# Arduino_MEGA_2560-Rev3_Shield.net
KiCad netlist of a schematic drawn in EAGLE
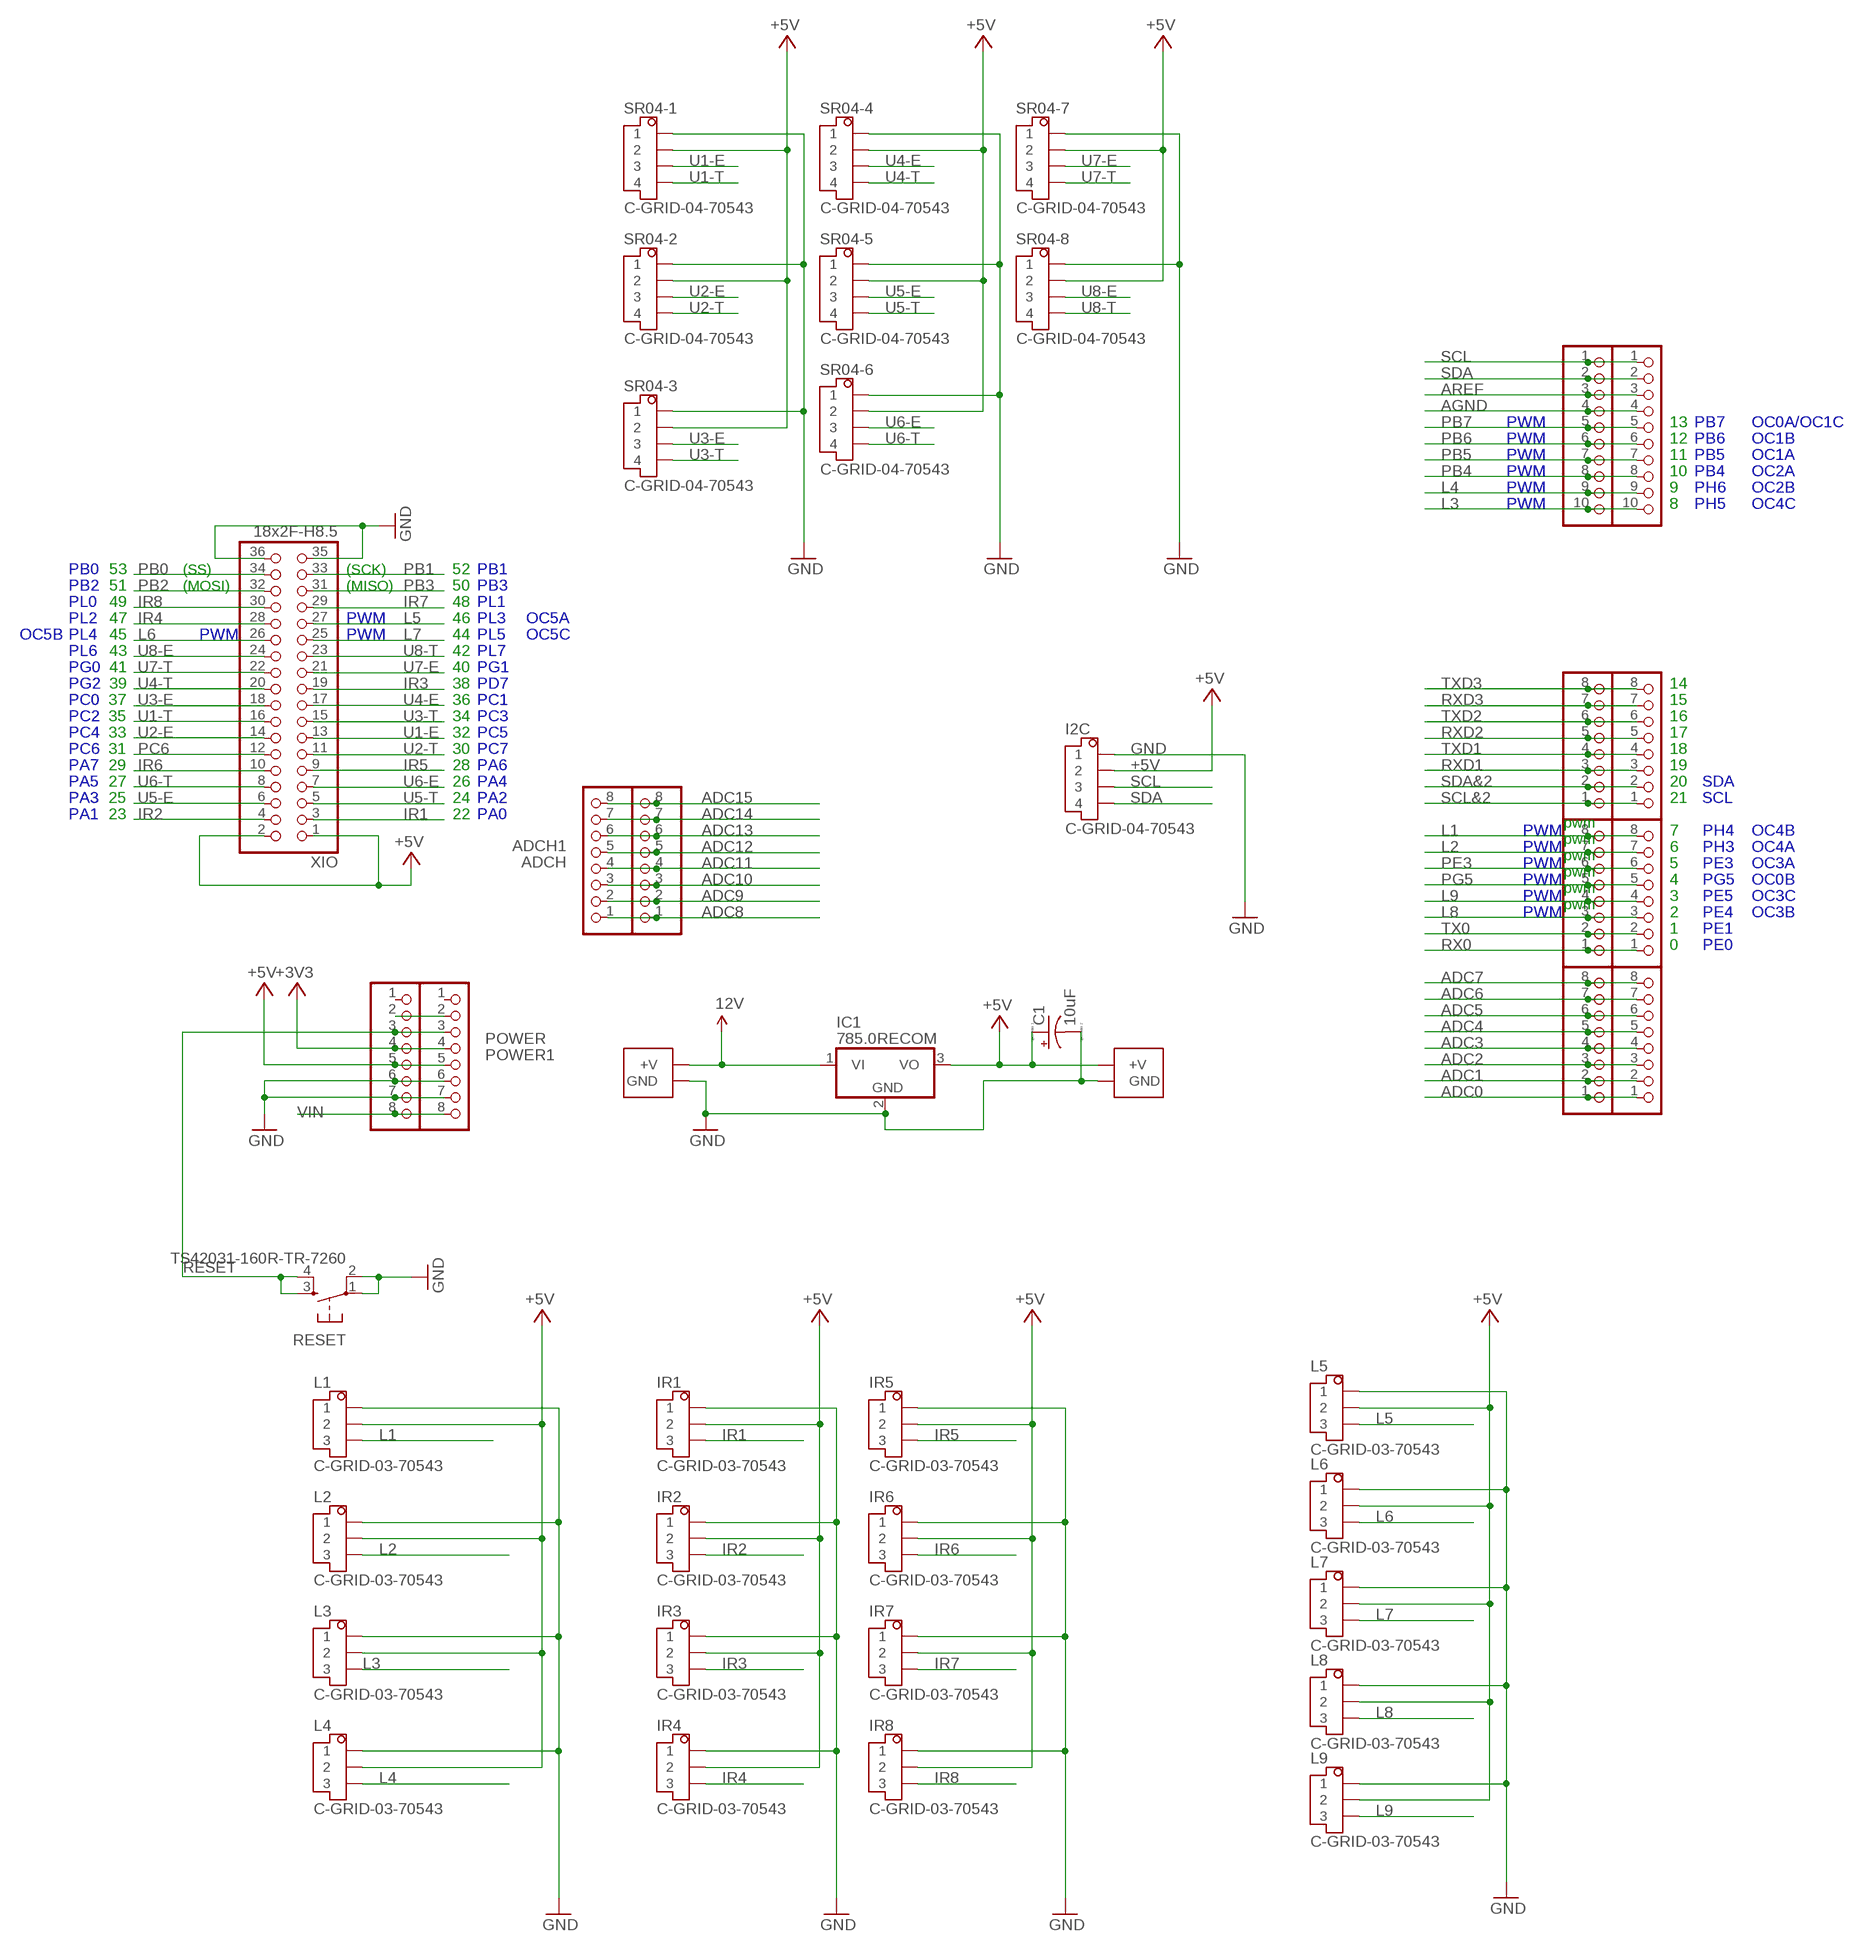
[diagram p0: schematic, sheet 1]

(export (version "E")
  (design (tool "Eeschema 10.0.6"))
  (components
    (comp (ref "ADCH")
      (value "8x1F-H8.5")
      (footprint "eagle-import:1X08")
      (libsource (lib "eagle-import") (part "PINHD-1X8"))
    )
    (comp (ref "ADCH1")
      (value "8x1F-H8.5")
      (footprint "eagle-import:1X08")
      (libsource (lib "eagle-import") (part "PINHD-1X8"))
    )
    (comp (ref "ADCL")
      (value "8x1F-H8.5")
      (footprint "eagle-import:1X08")
      (libsource (lib "eagle-import") (part "PINHD-1X8"))
    )
    (comp (ref "ADCL1")
      (value "8x1F-H8.5")
      (footprint "eagle-import:1X08")
      (libsource (lib "eagle-import") (part "PINHD-1X8"))
    )
    (comp (ref "C1")
      (value "10uF")
      (footprint "eagle-import:CT6032")
      (libsource (lib "eagle-import") (part "CPOL-USCT6032"))
    )
    (comp (ref "COMMUNICATION")
      (value "8x1F-H8.5")
      (footprint "eagle-import:1X08")
      (libsource (lib "eagle-import") (part "PINHD-1X8"))
    )
    (comp (ref "COMMUNICATION1")
      (value "8x1F-H8.5")
      (footprint "eagle-import:1X08")
      (libsource (lib "eagle-import") (part "PINHD-1X8"))
    )
    (comp (ref "I2C")
      (value "C-GRID-04-70543")
      (footprint "eagle-import:70543-04")
      (libsource (lib "eagle-import") (part "C-GRID-04-70543"))
    )
    (comp (ref "IC1")
      (value "785.0RECOM")
      (footprint "eagle-import:RECOM-78E")
      (libsource (lib "eagle-import") (part "78RECOM5.0"))
    )
    (comp (ref "IR1")
      (value "C-GRID-03-70543")
      (footprint "eagle-import:70543-03")
      (libsource (lib "eagle-import") (part "C-GRID-03-70543"))
    )
    (comp (ref "IR2")
      (value "C-GRID-03-70543")
      (footprint "eagle-import:70543-03")
      (libsource (lib "eagle-import") (part "C-GRID-03-70543"))
    )
    (comp (ref "IR3")
      (value "C-GRID-03-70543")
      (footprint "eagle-import:70543-03")
      (libsource (lib "eagle-import") (part "C-GRID-03-70543"))
    )
    (comp (ref "IR4")
      (value "C-GRID-03-70543")
      (footprint "eagle-import:70543-03")
      (libsource (lib "eagle-import") (part "C-GRID-03-70543"))
    )
    (comp (ref "IR5")
      (value "C-GRID-03-70543")
      (footprint "eagle-import:70543-03")
      (libsource (lib "eagle-import") (part "C-GRID-03-70543"))
    )
    (comp (ref "IR6")
      (value "C-GRID-03-70543")
      (footprint "eagle-import:70543-03")
      (libsource (lib "eagle-import") (part "C-GRID-03-70543"))
    )
    (comp (ref "IR7")
      (value "C-GRID-03-70543")
      (footprint "eagle-import:70543-03")
      (libsource (lib "eagle-import") (part "C-GRID-03-70543"))
    )
    (comp (ref "IR8")
      (value "C-GRID-03-70543")
      (footprint "eagle-import:70543-03")
      (libsource (lib "eagle-import") (part "C-GRID-03-70543"))
    )
    (comp (ref "JP1")
      (value "10x1F-H8.5")
      (footprint "eagle-import:1X10")
      (libsource (lib "eagle-import") (part "PINHD-1X10_ARD"))
    )
    (comp (ref "JP6")
      (value "10x1F-H8.5")
      (footprint "eagle-import:1X10")
      (libsource (lib "eagle-import") (part "PINHD-1X10_ARD"))
    )
    (comp (ref "L1")
      (value "C-GRID-03-70543")
      (footprint "eagle-import:70543-03")
      (libsource (lib "eagle-import") (part "C-GRID-03-70543"))
    )
    (comp (ref "L2")
      (value "C-GRID-03-70543")
      (footprint "eagle-import:70543-03")
      (libsource (lib "eagle-import") (part "C-GRID-03-70543"))
    )
    (comp (ref "L3")
      (value "C-GRID-03-70543")
      (footprint "eagle-import:70543-03")
      (libsource (lib "eagle-import") (part "C-GRID-03-70543"))
    )
    (comp (ref "L4")
      (value "C-GRID-03-70543")
      (footprint "eagle-import:70543-03")
      (libsource (lib "eagle-import") (part "C-GRID-03-70543"))
    )
    (comp (ref "L5")
      (value "C-GRID-03-70543")
      (footprint "eagle-import:70543-03")
      (libsource (lib "eagle-import") (part "C-GRID-03-70543"))
    )
    (comp (ref "L6")
      (value "C-GRID-03-70543")
      (footprint "eagle-import:70543-03")
      (libsource (lib "eagle-import") (part "C-GRID-03-70543"))
    )
    (comp (ref "L7")
      (value "C-GRID-03-70543")
      (footprint "eagle-import:70543-03")
      (libsource (lib "eagle-import") (part "C-GRID-03-70543"))
    )
    (comp (ref "L8")
      (value "C-GRID-03-70543")
      (footprint "eagle-import:70543-03")
      (libsource (lib "eagle-import") (part "C-GRID-03-70543"))
    )
    (comp (ref "L9")
      (value "C-GRID-03-70543")
      (footprint "eagle-import:70543-03")
      (libsource (lib "eagle-import") (part "C-GRID-03-70543"))
    )
    (comp (ref "POWER")
      (value "8x1F-H8.5")
      (footprint "eagle-import:1X08")
      (libsource (lib "eagle-import") (part "PINHD-1X8"))
    )
    (comp (ref "POWER1")
      (value "8x1F-H8.5")
      (footprint "eagle-import:1X08")
      (libsource (lib "eagle-import") (part "PINHD-1X8"))
    )
    (comp (ref "PWML")
      (value "8x1F-H8.5")
      (footprint "eagle-import:1X08")
      (libsource (lib "eagle-import") (part "PINHD-1X8"))
    )
    (comp (ref "PWML1")
      (value "8x1F-H8.5")
      (footprint "eagle-import:1X08")
      (libsource (lib "eagle-import") (part "PINHD-1X8"))
    )
    (comp (ref "RESET")
      (value "TS42031-160R-TR-7260")
      (footprint "eagle-import:TACTILE-PTH")
      (libsource (lib "eagle-import") (part "TAC_SWITCHPTH"))
    )
    (comp (ref "SR04-1")
      (value "C-GRID-04-70543")
      (footprint "eagle-import:70543-04")
      (libsource (lib "eagle-import") (part "C-GRID-04-70543"))
    )
    (comp (ref "SR04-2")
      (value "C-GRID-04-70543")
      (footprint "eagle-import:70543-04")
      (libsource (lib "eagle-import") (part "C-GRID-04-70543"))
    )
    (comp (ref "SR04-3")
      (value "C-GRID-04-70543")
      (footprint "eagle-import:70543-04")
      (libsource (lib "eagle-import") (part "C-GRID-04-70543"))
    )
    (comp (ref "SR04-4")
      (value "C-GRID-04-70543")
      (footprint "eagle-import:70543-04")
      (libsource (lib "eagle-import") (part "C-GRID-04-70543"))
    )
    (comp (ref "SR04-5")
      (value "C-GRID-04-70543")
      (footprint "eagle-import:70543-04")
      (libsource (lib "eagle-import") (part "C-GRID-04-70543"))
    )
    (comp (ref "SR04-6")
      (value "C-GRID-04-70543")
      (footprint "eagle-import:70543-04")
      (libsource (lib "eagle-import") (part "C-GRID-04-70543"))
    )
    (comp (ref "SR04-7")
      (value "C-GRID-04-70543")
      (footprint "eagle-import:70543-04")
      (libsource (lib "eagle-import") (part "C-GRID-04-70543"))
    )
    (comp (ref "SR04-8")
      (value "C-GRID-04-70543")
      (footprint "eagle-import:70543-04")
      (libsource (lib "eagle-import") (part "C-GRID-04-70543"))
    )
    (comp (ref "U$1")
      (value "POWERIN")
      (footprint "eagle-import:1825640000")
      (libsource (lib "eagle-import") (part "POWERIN"))
    )
    (comp (ref "U$2")
      (value "POWERIN")
      (footprint "eagle-import:1825640000")
      (libsource (lib "eagle-import") (part "POWERIN"))
    )
    (comp (ref "XIO")
      (value "18x2F-H8.5")
      (footprint "eagle-import:2X18")
      (libsource (lib "eagle-import") (part "PINHD-2X18"))
    )
  )
  (nets
    (net (code "1") (name "+3V3") (class "Default")
      (node (ref "POWER") (pin "4") (pinfunction "4_4") (pintype "passive"))
      (node (ref "POWER1") (pin "4") (pinfunction "4_4") (pintype "passive"))
    )
    (net (code "2") (name "+5V") (class "Default")
      (node (ref "C1") (pin "+") (pinfunction "+_+") (pintype "passive"))
      (node (ref "I2C") (pin "2") (pinfunction "2_2") (pintype "passive"))
      (node (ref "IC1") (pin "3") (pinfunction "VO_3") (pintype "passive"))
      (node (ref "IR1") (pin "2") (pinfunction "2_2") (pintype "passive"))
      (node (ref "IR2") (pin "2") (pinfunction "2_2") (pintype "passive"))
      (node (ref "IR3") (pin "2") (pinfunction "2_2") (pintype "passive"))
      (node (ref "IR4") (pin "2") (pinfunction "2_2") (pintype "passive"))
      (node (ref "IR5") (pin "2") (pinfunction "2_2") (pintype "passive"))
      (node (ref "IR6") (pin "2") (pinfunction "2_2") (pintype "passive"))
      (node (ref "IR7") (pin "2") (pinfunction "2_2") (pintype "passive"))
      (node (ref "IR8") (pin "2") (pinfunction "2_2") (pintype "passive"))
      (node (ref "L1") (pin "2") (pinfunction "2_2") (pintype "passive"))
      (node (ref "L2") (pin "2") (pinfunction "2_2") (pintype "passive"))
      (node (ref "L3") (pin "2") (pinfunction "2_2") (pintype "passive"))
      (node (ref "L4") (pin "2") (pinfunction "2_2") (pintype "passive"))
      (node (ref "L5") (pin "2") (pinfunction "2_2") (pintype "passive"))
      (node (ref "L6") (pin "2") (pinfunction "2_2") (pintype "passive"))
      (node (ref "L7") (pin "2") (pinfunction "2_2") (pintype "passive"))
      (node (ref "L8") (pin "2") (pinfunction "2_2") (pintype "passive"))
      (node (ref "L9") (pin "2") (pinfunction "2_2") (pintype "passive"))
      (node (ref "POWER") (pin "5") (pinfunction "5_5") (pintype "passive"))
      (node (ref "POWER1") (pin "5") (pinfunction "5_5") (pintype "passive"))
      (node (ref "SR04-1") (pin "2") (pinfunction "2_2") (pintype "passive"))
      (node (ref "SR04-2") (pin "2") (pinfunction "2_2") (pintype "passive"))
      (node (ref "SR04-3") (pin "2") (pinfunction "2_2") (pintype "passive"))
      (node (ref "SR04-4") (pin "2") (pinfunction "2_2") (pintype "passive"))
      (node (ref "SR04-5") (pin "2") (pinfunction "2_2") (pintype "passive"))
      (node (ref "SR04-6") (pin "2") (pinfunction "2_2") (pintype "passive"))
      (node (ref "SR04-7") (pin "2") (pinfunction "2_2") (pintype "passive"))
      (node (ref "SR04-8") (pin "2") (pinfunction "2_2") (pintype "passive"))
      (node (ref "U$2") (pin "B1") (pinfunction "+V_B1") (pintype "bidirectional"))
      (node (ref "U$2") (pin "B2") (pinfunction "+V_B2") (pintype "bidirectional"))
      (node (ref "XIO") (pin "1") (pinfunction "1_1") (pintype "passive"))
      (node (ref "XIO") (pin "2") (pinfunction "2_2") (pintype "passive"))
    )
    (net (code "3") (name "/ADC0") (class "Default")
      (node (ref "ADCL") (pin "1") (pinfunction "1_1") (pintype "passive"))
      (node (ref "ADCL1") (pin "1") (pinfunction "1_1") (pintype "passive"))
    )
    (net (code "4") (name "/ADC1") (class "Default")
      (node (ref "ADCL") (pin "2") (pinfunction "2_2") (pintype "passive"))
      (node (ref "ADCL1") (pin "2") (pinfunction "2_2") (pintype "passive"))
    )
    (net (code "5") (name "/ADC2") (class "Default")
      (node (ref "ADCL") (pin "3") (pinfunction "3_3") (pintype "passive"))
      (node (ref "ADCL1") (pin "3") (pinfunction "3_3") (pintype "passive"))
    )
    (net (code "6") (name "/ADC3") (class "Default")
      (node (ref "ADCL") (pin "4") (pinfunction "4_4") (pintype "passive"))
      (node (ref "ADCL1") (pin "4") (pinfunction "4_4") (pintype "passive"))
    )
    (net (code "7") (name "/ADC4") (class "Default")
      (node (ref "ADCL") (pin "5") (pinfunction "5_5") (pintype "passive"))
      (node (ref "ADCL1") (pin "5") (pinfunction "5_5") (pintype "passive"))
    )
    (net (code "8") (name "/ADC5") (class "Default")
      (node (ref "ADCL") (pin "6") (pinfunction "6_6") (pintype "passive"))
      (node (ref "ADCL1") (pin "6") (pinfunction "6_6") (pintype "passive"))
    )
    (net (code "9") (name "/ADC6") (class "Default")
      (node (ref "ADCL") (pin "7") (pinfunction "7_7") (pintype "passive"))
      (node (ref "ADCL1") (pin "7") (pinfunction "7_7") (pintype "passive"))
    )
    (net (code "10") (name "/ADC7") (class "Default")
      (node (ref "ADCL") (pin "8") (pinfunction "8_8") (pintype "passive"))
      (node (ref "ADCL1") (pin "8") (pinfunction "8_8") (pintype "passive"))
    )
    (net (code "11") (name "/ADC8") (class "Default")
      (node (ref "ADCH") (pin "1") (pinfunction "1_1") (pintype "passive"))
      (node (ref "ADCH1") (pin "1") (pinfunction "1_1") (pintype "passive"))
    )
    (net (code "12") (name "/ADC9") (class "Default")
      (node (ref "ADCH") (pin "2") (pinfunction "2_2") (pintype "passive"))
      (node (ref "ADCH1") (pin "2") (pinfunction "2_2") (pintype "passive"))
    )
    (net (code "13") (name "/ADC10") (class "Default")
      (node (ref "ADCH") (pin "3") (pinfunction "3_3") (pintype "passive"))
      (node (ref "ADCH1") (pin "3") (pinfunction "3_3") (pintype "passive"))
    )
    (net (code "14") (name "/ADC11") (class "Default")
      (node (ref "ADCH") (pin "4") (pinfunction "4_4") (pintype "passive"))
      (node (ref "ADCH1") (pin "4") (pinfunction "4_4") (pintype "passive"))
    )
    (net (code "15") (name "/ADC12") (class "Default")
      (node (ref "ADCH") (pin "5") (pinfunction "5_5") (pintype "passive"))
      (node (ref "ADCH1") (pin "5") (pinfunction "5_5") (pintype "passive"))
    )
    (net (code "16") (name "/ADC13") (class "Default")
      (node (ref "ADCH") (pin "6") (pinfunction "6_6") (pintype "passive"))
      (node (ref "ADCH1") (pin "6") (pinfunction "6_6") (pintype "passive"))
    )
    (net (code "17") (name "/ADC14") (class "Default")
      (node (ref "ADCH") (pin "7") (pinfunction "7_7") (pintype "passive"))
      (node (ref "ADCH1") (pin "7") (pinfunction "7_7") (pintype "passive"))
    )
    (net (code "18") (name "/ADC15") (class "Default")
      (node (ref "ADCH") (pin "8") (pinfunction "8_8") (pintype "passive"))
      (node (ref "ADCH1") (pin "8") (pinfunction "8_8") (pintype "passive"))
    )
    (net (code "19") (name "/AGND") (class "Default")
      (node (ref "JP1") (pin "4") (pinfunction "4_4") (pintype "passive"))
      (node (ref "JP6") (pin "4") (pinfunction "4_4") (pintype "passive"))
    )
    (net (code "20") (name "/AREF") (class "Default")
      (node (ref "JP1") (pin "3") (pinfunction "3_3") (pintype "passive"))
      (node (ref "JP6") (pin "3") (pinfunction "3_3") (pintype "passive"))
    )
    (net (code "21") (name "/IR1") (class "Default")
      (node (ref "IR1") (pin "3") (pinfunction "3_3") (pintype "passive"))
      (node (ref "XIO") (pin "3") (pinfunction "3_3") (pintype "passive"))
    )
    (net (code "22") (name "/IR2") (class "Default")
      (node (ref "IR2") (pin "3") (pinfunction "3_3") (pintype "passive"))
      (node (ref "XIO") (pin "4") (pinfunction "4_4") (pintype "passive"))
    )
    (net (code "23") (name "/IR3") (class "Default")
      (node (ref "IR3") (pin "3") (pinfunction "3_3") (pintype "passive"))
      (node (ref "XIO") (pin "19") (pinfunction "19_19") (pintype "passive"))
    )
    (net (code "24") (name "/IR4") (class "Default")
      (node (ref "IR4") (pin "3") (pinfunction "3_3") (pintype "passive"))
      (node (ref "XIO") (pin "28") (pinfunction "28_28") (pintype "passive"))
    )
    (net (code "25") (name "/IR5") (class "Default")
      (node (ref "IR5") (pin "3") (pinfunction "3_3") (pintype "passive"))
      (node (ref "XIO") (pin "9") (pinfunction "9_9") (pintype "passive"))
    )
    (net (code "26") (name "/IR6") (class "Default")
      (node (ref "IR6") (pin "3") (pinfunction "3_3") (pintype "passive"))
      (node (ref "XIO") (pin "10") (pinfunction "10_10") (pintype "passive"))
    )
    (net (code "27") (name "/IR7") (class "Default")
      (node (ref "IR7") (pin "3") (pinfunction "3_3") (pintype "passive"))
      (node (ref "XIO") (pin "29") (pinfunction "29_29") (pintype "passive"))
    )
    (net (code "28") (name "/IR8") (class "Default")
      (node (ref "IR8") (pin "3") (pinfunction "3_3") (pintype "passive"))
      (node (ref "XIO") (pin "30") (pinfunction "30_30") (pintype "passive"))
    )
    (net (code "29") (name "/L1") (class "Default")
      (node (ref "L1") (pin "3") (pinfunction "3_3") (pintype "passive"))
      (node (ref "PWML") (pin "8") (pinfunction "8_8") (pintype "passive"))
      (node (ref "PWML1") (pin "8") (pinfunction "8_8") (pintype "passive"))
    )
    (net (code "30") (name "/L2") (class "Default")
      (node (ref "L2") (pin "3") (pinfunction "3_3") (pintype "passive"))
      (node (ref "PWML") (pin "7") (pinfunction "7_7") (pintype "passive"))
      (node (ref "PWML1") (pin "7") (pinfunction "7_7") (pintype "passive"))
    )
    (net (code "31") (name "/L3") (class "Default")
      (node (ref "JP1") (pin "10") (pinfunction "10_10") (pintype "passive"))
      (node (ref "JP6") (pin "10") (pinfunction "10_10") (pintype "passive"))
      (node (ref "L3") (pin "3") (pinfunction "3_3") (pintype "passive"))
    )
    (net (code "32") (name "/L4") (class "Default")
      (node (ref "JP1") (pin "9") (pinfunction "9_9") (pintype "passive"))
      (node (ref "JP6") (pin "9") (pinfunction "9_9") (pintype "passive"))
      (node (ref "L4") (pin "3") (pinfunction "3_3") (pintype "passive"))
    )
    (net (code "33") (name "/L5") (class "Default")
      (node (ref "L5") (pin "3") (pinfunction "3_3") (pintype "passive"))
      (node (ref "XIO") (pin "27") (pinfunction "27_27") (pintype "passive"))
    )
    (net (code "34") (name "/L6") (class "Default")
      (node (ref "L6") (pin "3") (pinfunction "3_3") (pintype "passive"))
      (node (ref "XIO") (pin "26") (pinfunction "26_26") (pintype "passive"))
    )
    (net (code "35") (name "/L7") (class "Default")
      (node (ref "L7") (pin "3") (pinfunction "3_3") (pintype "passive"))
      (node (ref "XIO") (pin "25") (pinfunction "25_25") (pintype "passive"))
    )
    (net (code "36") (name "/L8") (class "Default")
      (node (ref "L8") (pin "3") (pinfunction "3_3") (pintype "passive"))
      (node (ref "PWML") (pin "3") (pinfunction "3_3") (pintype "passive"))
      (node (ref "PWML1") (pin "3") (pinfunction "3_3") (pintype "passive"))
    )
    (net (code "37") (name "/L9") (class "Default")
      (node (ref "L9") (pin "3") (pinfunction "3_3") (pintype "passive"))
      (node (ref "PWML") (pin "4") (pinfunction "4_4") (pintype "passive"))
      (node (ref "PWML1") (pin "4") (pinfunction "4_4") (pintype "passive"))
    )
    (net (code "38") (name "/PB0") (class "Default")
      (node (ref "XIO") (pin "34") (pinfunction "34_34") (pintype "passive"))
    )
    (net (code "39") (name "/PB1") (class "Default")
      (node (ref "XIO") (pin "33") (pinfunction "33_33") (pintype "passive"))
    )
    (net (code "40") (name "/PB2") (class "Default")
      (node (ref "XIO") (pin "32") (pinfunction "32_32") (pintype "passive"))
    )
    (net (code "41") (name "/PB3") (class "Default")
      (node (ref "XIO") (pin "31") (pinfunction "31_31") (pintype "passive"))
    )
    (net (code "42") (name "/PB4") (class "Default")
      (node (ref "JP1") (pin "8") (pinfunction "8_8") (pintype "passive"))
      (node (ref "JP6") (pin "8") (pinfunction "8_8") (pintype "passive"))
    )
    (net (code "43") (name "/PB5") (class "Default")
      (node (ref "JP1") (pin "7") (pinfunction "7_7") (pintype "passive"))
      (node (ref "JP6") (pin "7") (pinfunction "7_7") (pintype "passive"))
    )
    (net (code "44") (name "/PB6") (class "Default")
      (node (ref "JP1") (pin "6") (pinfunction "6_6") (pintype "passive"))
      (node (ref "JP6") (pin "6") (pinfunction "6_6") (pintype "passive"))
    )
    (net (code "45") (name "/PB7") (class "Default")
      (node (ref "JP1") (pin "5") (pinfunction "5_5") (pintype "passive"))
      (node (ref "JP6") (pin "5") (pinfunction "5_5") (pintype "passive"))
    )
    (net (code "46") (name "/PC6") (class "Default")
      (node (ref "XIO") (pin "12") (pinfunction "12_12") (pintype "passive"))
    )
    (net (code "47") (name "/PE3") (class "Default")
      (node (ref "PWML") (pin "6") (pinfunction "6_6") (pintype "passive"))
      (node (ref "PWML1") (pin "6") (pinfunction "6_6") (pintype "passive"))
    )
    (net (code "48") (name "/PG5") (class "Default")
      (node (ref "PWML") (pin "5") (pinfunction "5_5") (pintype "passive"))
      (node (ref "PWML1") (pin "5") (pinfunction "5_5") (pintype "passive"))
    )
    (net (code "49") (name "/RESET") (class "Default")
      (node (ref "POWER") (pin "3") (pinfunction "3_3") (pintype "passive"))
      (node (ref "POWER1") (pin "3") (pinfunction "3_3") (pintype "passive"))
      (node (ref "RESET") (pin "3") (pinfunction "3_3") (pintype "passive"))
      (node (ref "RESET") (pin "4") (pinfunction "4_4") (pintype "passive"))
    )
    (net (code "50") (name "/RX0") (class "Default")
      (node (ref "PWML") (pin "1") (pinfunction "1_1") (pintype "passive"))
      (node (ref "PWML1") (pin "1") (pinfunction "1_1") (pintype "passive"))
    )
    (net (code "51") (name "/RXD1") (class "Default")
      (node (ref "COMMUNICATION") (pin "3") (pinfunction "3_3") (pintype "passive"))
      (node (ref "COMMUNICATION1") (pin "3") (pinfunction "3_3") (pintype "passive"))
    )
    (net (code "52") (name "/RXD2") (class "Default")
      (node (ref "COMMUNICATION") (pin "5") (pinfunction "5_5") (pintype "passive"))
      (node (ref "COMMUNICATION1") (pin "5") (pinfunction "5_5") (pintype "passive"))
    )
    (net (code "53") (name "/RXD3") (class "Default")
      (node (ref "COMMUNICATION") (pin "7") (pinfunction "7_7") (pintype "passive"))
      (node (ref "COMMUNICATION1") (pin "7") (pinfunction "7_7") (pintype "passive"))
    )
    (net (code "54") (name "/SCL") (class "Default")
      (node (ref "I2C") (pin "3") (pinfunction "3_3") (pintype "passive"))
      (node (ref "JP1") (pin "1") (pinfunction "1_1") (pintype "passive"))
      (node (ref "JP6") (pin "1") (pinfunction "1_1") (pintype "passive"))
    )
    (net (code "55") (name "/SCL&2") (class "Default")
      (node (ref "COMMUNICATION") (pin "1") (pinfunction "1_1") (pintype "passive"))
      (node (ref "COMMUNICATION1") (pin "1") (pinfunction "1_1") (pintype "passive"))
    )
    (net (code "56") (name "/SDA") (class "Default")
      (node (ref "I2C") (pin "4") (pinfunction "4_4") (pintype "passive"))
      (node (ref "JP1") (pin "2") (pinfunction "2_2") (pintype "passive"))
      (node (ref "JP6") (pin "2") (pinfunction "2_2") (pintype "passive"))
    )
    (net (code "57") (name "/SDA&2") (class "Default")
      (node (ref "COMMUNICATION") (pin "2") (pinfunction "2_2") (pintype "passive"))
      (node (ref "COMMUNICATION1") (pin "2") (pinfunction "2_2") (pintype "passive"))
    )
    (net (code "58") (name "/TX0") (class "Default")
      (node (ref "PWML") (pin "2") (pinfunction "2_2") (pintype "passive"))
      (node (ref "PWML1") (pin "2") (pinfunction "2_2") (pintype "passive"))
    )
    (net (code "59") (name "/TXD1") (class "Default")
      (node (ref "COMMUNICATION") (pin "4") (pinfunction "4_4") (pintype "passive"))
      (node (ref "COMMUNICATION1") (pin "4") (pinfunction "4_4") (pintype "passive"))
    )
    (net (code "60") (name "/TXD2") (class "Default")
      (node (ref "COMMUNICATION") (pin "6") (pinfunction "6_6") (pintype "passive"))
      (node (ref "COMMUNICATION1") (pin "6") (pinfunction "6_6") (pintype "passive"))
    )
    (net (code "61") (name "/TXD3") (class "Default")
      (node (ref "COMMUNICATION") (pin "8") (pinfunction "8_8") (pintype "passive"))
      (node (ref "COMMUNICATION1") (pin "8") (pinfunction "8_8") (pintype "passive"))
    )
    (net (code "62") (name "/U1-E") (class "Default")
      (node (ref "SR04-1") (pin "3") (pinfunction "3_3") (pintype "passive"))
      (node (ref "XIO") (pin "13") (pinfunction "13_13") (pintype "passive"))
    )
    (net (code "63") (name "/U1-T") (class "Default")
      (node (ref "SR04-1") (pin "4") (pinfunction "4_4") (pintype "passive"))
      (node (ref "XIO") (pin "16") (pinfunction "16_16") (pintype "passive"))
    )
    (net (code "64") (name "/U2-E") (class "Default")
      (node (ref "SR04-2") (pin "3") (pinfunction "3_3") (pintype "passive"))
      (node (ref "XIO") (pin "14") (pinfunction "14_14") (pintype "passive"))
    )
    (net (code "65") (name "/U2-T") (class "Default")
      (node (ref "SR04-2") (pin "4") (pinfunction "4_4") (pintype "passive"))
      (node (ref "XIO") (pin "11") (pinfunction "11_11") (pintype "passive"))
    )
    (net (code "66") (name "/U3-E") (class "Default")
      (node (ref "SR04-3") (pin "3") (pinfunction "3_3") (pintype "passive"))
      (node (ref "XIO") (pin "18") (pinfunction "18_18") (pintype "passive"))
    )
    (net (code "67") (name "/U3-T") (class "Default")
      (node (ref "SR04-3") (pin "4") (pinfunction "4_4") (pintype "passive"))
      (node (ref "XIO") (pin "15") (pinfunction "15_15") (pintype "passive"))
    )
    (net (code "68") (name "/U4-E") (class "Default")
      (node (ref "SR04-4") (pin "3") (pinfunction "3_3") (pintype "passive"))
      (node (ref "XIO") (pin "17") (pinfunction "17_17") (pintype "passive"))
    )
    (net (code "69") (name "/U4-T") (class "Default")
      (node (ref "SR04-4") (pin "4") (pinfunction "4_4") (pintype "passive"))
      (node (ref "XIO") (pin "20") (pinfunction "20_20") (pintype "passive"))
    )
    (net (code "70") (name "/U5-E") (class "Default")
      (node (ref "SR04-5") (pin "3") (pinfunction "3_3") (pintype "passive"))
      (node (ref "XIO") (pin "6") (pinfunction "6_6") (pintype "passive"))
    )
    (net (code "71") (name "/U5-T") (class "Default")
      (node (ref "SR04-5") (pin "4") (pinfunction "4_4") (pintype "passive"))
      (node (ref "XIO") (pin "5") (pinfunction "5_5") (pintype "passive"))
    )
    (net (code "72") (name "/U6-E") (class "Default")
      (node (ref "SR04-6") (pin "3") (pinfunction "3_3") (pintype "passive"))
      (node (ref "XIO") (pin "7") (pinfunction "7_7") (pintype "passive"))
    )
    (net (code "73") (name "/U6-T") (class "Default")
      (node (ref "SR04-6") (pin "4") (pinfunction "4_4") (pintype "passive"))
      (node (ref "XIO") (pin "8") (pinfunction "8_8") (pintype "passive"))
    )
    (net (code "74") (name "/U7-E") (class "Default")
      (node (ref "SR04-7") (pin "3") (pinfunction "3_3") (pintype "passive"))
      (node (ref "XIO") (pin "21") (pinfunction "21_21") (pintype "passive"))
    )
    (net (code "75") (name "/U7-T") (class "Default")
      (node (ref "SR04-7") (pin "4") (pinfunction "4_4") (pintype "passive"))
      (node (ref "XIO") (pin "22") (pinfunction "22_22") (pintype "passive"))
    )
    (net (code "76") (name "/U8-E") (class "Default")
      (node (ref "SR04-8") (pin "3") (pinfunction "3_3") (pintype "passive"))
      (node (ref "XIO") (pin "24") (pinfunction "24_24") (pintype "passive"))
    )
    (net (code "77") (name "/U8-T") (class "Default")
      (node (ref "SR04-8") (pin "4") (pinfunction "4_4") (pintype "passive"))
      (node (ref "XIO") (pin "23") (pinfunction "23_23") (pintype "passive"))
    )
    (net (code "78") (name "/VIN") (class "Default")
      (node (ref "POWER") (pin "8") (pinfunction "8_8") (pintype "passive"))
      (node (ref "POWER1") (pin "8") (pinfunction "8_8") (pintype "passive"))
    )
    (net (code "79") (name "12V") (class "Default")
      (node (ref "IC1") (pin "1") (pinfunction "VI_1") (pintype "input"))
      (node (ref "U$1") (pin "B1") (pinfunction "+V_B1") (pintype "bidirectional"))
      (node (ref "U$1") (pin "B2") (pinfunction "+V_B2") (pintype "bidirectional"))
    )
    (net (code "80") (name "GND") (class "Default")
      (node (ref "C1") (pin "-") (pinfunction "-_-") (pintype "passive"))
      (node (ref "I2C") (pin "1") (pinfunction "1_1") (pintype "passive"))
      (node (ref "IC1") (pin "2") (pinfunction "GND_2") (pintype "passive"))
      (node (ref "IR1") (pin "1") (pinfunction "1_1") (pintype "passive"))
      (node (ref "IR2") (pin "1") (pinfunction "1_1") (pintype "passive"))
      (node (ref "IR3") (pin "1") (pinfunction "1_1") (pintype "passive"))
      (node (ref "IR4") (pin "1") (pinfunction "1_1") (pintype "passive"))
      (node (ref "IR5") (pin "1") (pinfunction "1_1") (pintype "passive"))
      (node (ref "IR6") (pin "1") (pinfunction "1_1") (pintype "passive"))
      (node (ref "IR7") (pin "1") (pinfunction "1_1") (pintype "passive"))
      (node (ref "IR8") (pin "1") (pinfunction "1_1") (pintype "passive"))
      (node (ref "L1") (pin "1") (pinfunction "1_1") (pintype "passive"))
      (node (ref "L2") (pin "1") (pinfunction "1_1") (pintype "passive"))
      (node (ref "L3") (pin "1") (pinfunction "1_1") (pintype "passive"))
      (node (ref "L4") (pin "1") (pinfunction "1_1") (pintype "passive"))
      (node (ref "L5") (pin "1") (pinfunction "1_1") (pintype "passive"))
      (node (ref "L6") (pin "1") (pinfunction "1_1") (pintype "passive"))
      (node (ref "L7") (pin "1") (pinfunction "1_1") (pintype "passive"))
      (node (ref "L8") (pin "1") (pinfunction "1_1") (pintype "passive"))
      (node (ref "L9") (pin "1") (pinfunction "1_1") (pintype "passive"))
      (node (ref "POWER") (pin "6") (pinfunction "6_6") (pintype "passive"))
      (node (ref "POWER") (pin "7") (pinfunction "7_7") (pintype "passive"))
      (node (ref "POWER1") (pin "6") (pinfunction "6_6") (pintype "passive"))
      (node (ref "POWER1") (pin "7") (pinfunction "7_7") (pintype "passive"))
      (node (ref "RESET") (pin "1") (pinfunction "1_1") (pintype "passive"))
      (node (ref "RESET") (pin "2") (pinfunction "2_2") (pintype "passive"))
      (node (ref "SR04-1") (pin "1") (pinfunction "1_1") (pintype "passive"))
      (node (ref "SR04-2") (pin "1") (pinfunction "1_1") (pintype "passive"))
      (node (ref "SR04-3") (pin "1") (pinfunction "1_1") (pintype "passive"))
      (node (ref "SR04-4") (pin "1") (pinfunction "1_1") (pintype "passive"))
      (node (ref "SR04-5") (pin "1") (pinfunction "1_1") (pintype "passive"))
      (node (ref "SR04-6") (pin "1") (pinfunction "1_1") (pintype "passive"))
      (node (ref "SR04-7") (pin "1") (pinfunction "1_1") (pintype "passive"))
      (node (ref "SR04-8") (pin "1") (pinfunction "1_1") (pintype "passive"))
      (node (ref "U$1") (pin "A1") (pinfunction "GND_A1") (pintype "bidirectional"))
      (node (ref "U$1") (pin "A2") (pinfunction "GND_A2") (pintype "bidirectional"))
      (node (ref "U$2") (pin "A1") (pinfunction "GND_A1") (pintype "bidirectional"))
      (node (ref "U$2") (pin "A2") (pinfunction "GND_A2") (pintype "bidirectional"))
      (node (ref "XIO") (pin "35") (pinfunction "35_35") (pintype "passive"))
      (node (ref "XIO") (pin "36") (pinfunction "36_36") (pintype "passive"))
    )
    (net (code "81") (name "Net-(POWER-Pad2)") (class "Default")
      (node (ref "POWER") (pin "2") (pinfunction "2_2") (pintype "passive"))
      (node (ref "POWER1") (pin "2") (pinfunction "2_2") (pintype "passive"))
    )
    (net (code "82") (name "unconnected-(POWER-Pad1)") (class "Default")
      (node (ref "POWER") (pin "1") (pinfunction "1_1") (pintype "passive"))
    )
    (net (code "83") (name "unconnected-(POWER1-Pad1)") (class "Default")
      (node (ref "POWER1") (pin "1") (pinfunction "1_1") (pintype "passive"))
    )
  )
)
